# NB2_PSU.net
KiCad netlist of a schematic drawn in Altium Designer
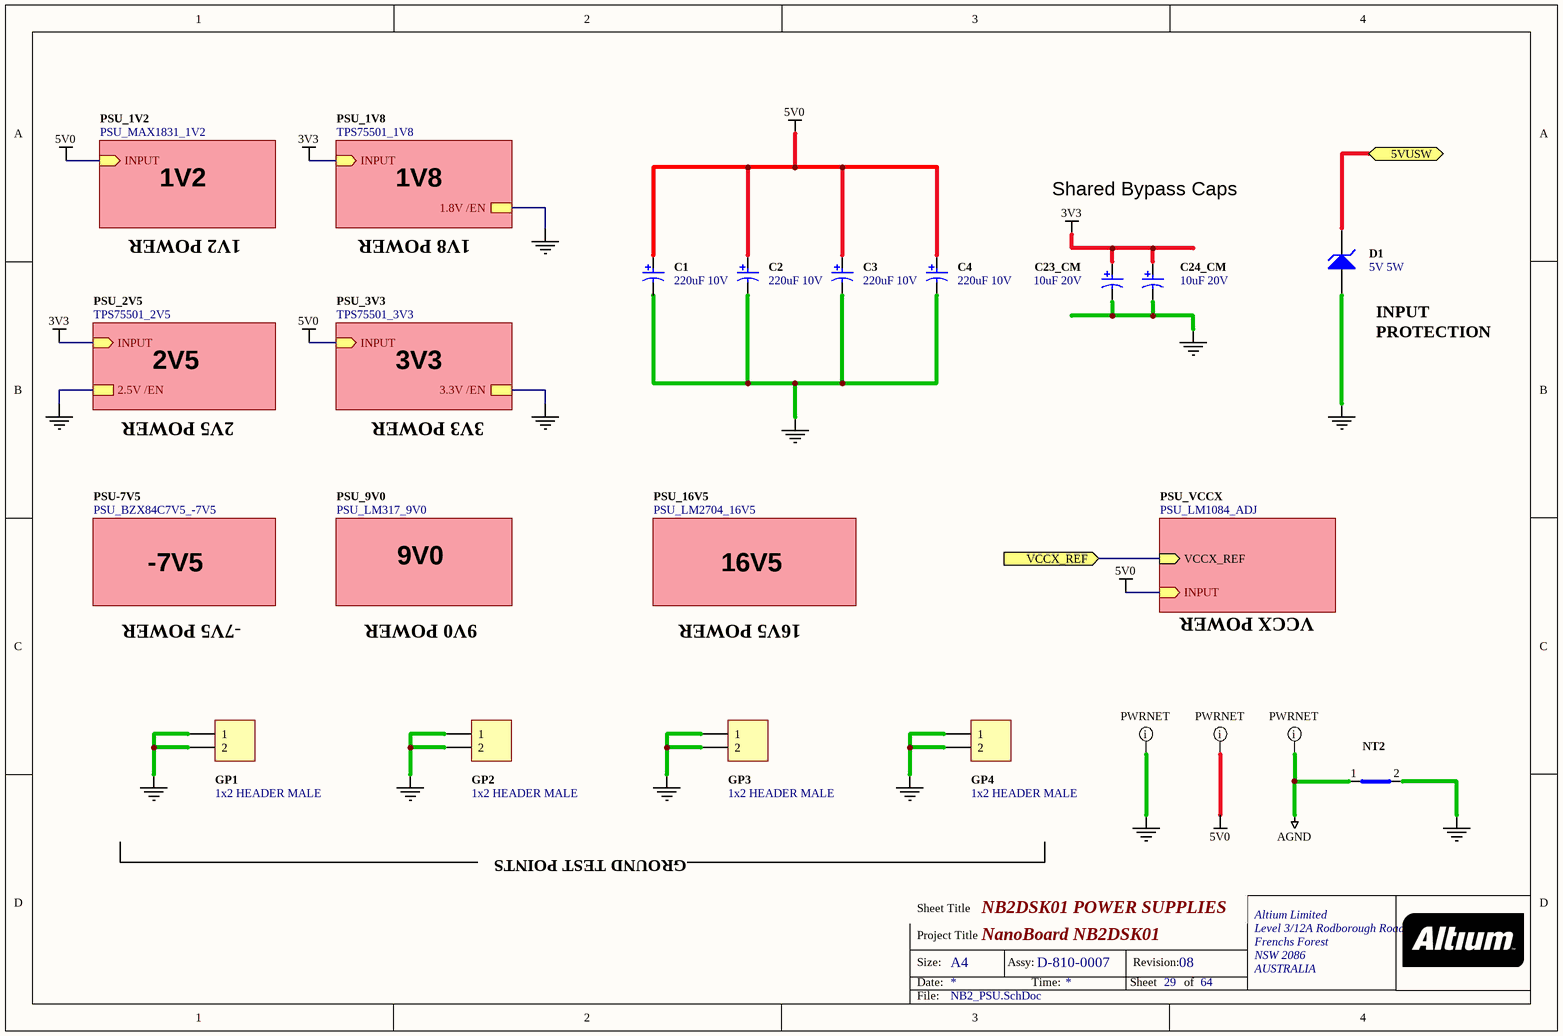
[diagram p0: NB2_PSU.SchDoc]

(export (version "E")
  (design (tool "Eeschema 10.0.6"))
  (components
    (comp (ref "C1")
      (value "220uF 10V")
      (footprint "CAPC7343-STAR")
      (description "Capacitor, Tantalum, 220uF 10% 10V MCCT-D (7343-31)")
      (fields (field (name "TOLERANCE") "10 %"))
      (libsource (lib "altium-import") (part "root_0_CAP-P_"))
    )
    (comp (ref "C2")
      (value "220uF 10V")
      (footprint "CAPC7343-STAR")
      (description "Capacitor, Tantalum, 220uF 10% 10V MCCT-D (7343-31)")
      (fields (field (name "TOLERANCE") "10 %"))
      (libsource (lib "altium-import") (part "root_0_CAP-P_"))
    )
    (comp (ref "C3")
      (value "220uF 10V")
      (footprint "CAPC7343-STAR")
      (description "Capacitor, Tantalum, 220uF 10% 10V MCCT-D (7343-31)")
      (fields (field (name "TOLERANCE") "10 %"))
      (libsource (lib "altium-import") (part "root_0_CAP-P_"))
    )
    (comp (ref "C4")
      (value "220uF 10V")
      (footprint "CAPC7343-STAR")
      (description "Capacitor, Tantalum, 220uF 10% 10V MCCT-D (7343-31)")
      (fields (field (name "TOLERANCE") "10 %"))
      (libsource (lib "altium-import") (part "root_0_CAP-P_"))
    )
    (comp (ref "C23_CM")
      (value "10uF 20V")
      (footprint "CAPC3528-STAR")
      (description "Capacitor, Tantalum, 10uF 10% 20V MCCT-B (3528)")
      (fields (field (name "TOLERANCE") "10 %"))
      (libsource (lib "altium-import") (part "root_0_CAP-P_"))
    )
    (comp (ref "C24_CM")
      (value "10uF 20V")
      (footprint "CAPC3528-STAR")
      (description "Capacitor, Tantalum, 10uF 10% 20V MCCT-B (3528)")
      (fields (field (name "TOLERANCE") "10 %"))
      (libsource (lib "altium-import") (part "root_0_CAP-P_"))
    )
    (comp (ref "D1")
      (value "5V 5W")
      (footprint "DIOM8059")
      (description "Zener Diode, 5V 5W")
      (libsource (lib "altium-import") (part "root_1_DIO-ZENER-1-2_"))
    )
    (comp (ref "GP1")
      (value "1x2 HEADER MALE")
      (footprint "HDR1X2")
      (description "Header IDC, 2 x 1 Pin Vertical 2.54mm Pitch (Non-Boxed, Male)")
      (libsource (lib "altium-import") (part "root_0_CON-HDR-1x2-STR_"))
    )
    (comp (ref "GP2")
      (value "1x2 HEADER MALE")
      (footprint "HDR1X2")
      (description "Header IDC, 2 x 1 Pin Vertical 2.54mm Pitch (Non-Boxed, Male)")
      (libsource (lib "altium-import") (part "root_0_CON-HDR-1x2-STR_"))
    )
    (comp (ref "GP3")
      (value "1x2 HEADER MALE")
      (footprint "HDR1X2")
      (description "Header IDC, 2 x 1 Pin Vertical 2.54mm Pitch (Non-Boxed, Male)")
      (libsource (lib "altium-import") (part "root_0_CON-HDR-1x2-STR_"))
    )
    (comp (ref "GP4")
      (value "1x2 HEADER MALE")
      (footprint "HDR1X2")
      (description "Header IDC, 2 x 1 Pin Vertical 2.54mm Pitch (Non-Boxed, Male)")
      (libsource (lib "altium-import") (part "root_0_CON-HDR-1x2-STR_"))
    )
    (comp (ref "NT2")
      (value "Net Tie SMT2")
      (footprint "NETTIE-SMT2-31X51")
      (description "Net-Tie, Surface Mount, 2 x 1.6mm x 0.8mm SMT Pads - For 0.8mm Track")
      (libsource (lib "AltiumDesignLibrary") (part "NETTIE-SMT2"))
    )
  )
  (nets
    (net (code "1") (name "/5VUSW") (class "Default")
      (node (ref "D1") (pin "2") (pinfunction "K_2") (pintype "passive"))
    )
    (net (code "3") (name "3V3") (class "Default")
      (node (ref "C23_CM") (pin "1") (pinfunction "1_1") (pintype "passive"))
      (node (ref "C24_CM") (pin "1") (pinfunction "1_1") (pintype "passive"))
    )
    (net (code "4") (name "5V0") (class "Default")
      (node (ref "C1") (pin "1") (pinfunction "1_1") (pintype "passive"))
      (node (ref "C2") (pin "1") (pinfunction "1_1") (pintype "passive"))
      (node (ref "C3") (pin "1") (pinfunction "1_1") (pintype "passive"))
      (node (ref "C4") (pin "1") (pinfunction "1_1") (pintype "passive"))
    )
    (net (code "5") (name "AGND") (class "Default")
      (node (ref "NT2") (pin "1") (pinfunction "Net1_1") (pintype "passive"))
    )
    (net (code "6") (name "GND") (class "Default")
      (node (ref "C1") (pin "2") (pinfunction "2_2") (pintype "passive"))
      (node (ref "C2") (pin "2") (pinfunction "2_2") (pintype "passive"))
      (node (ref "C23_CM") (pin "2") (pinfunction "2_2") (pintype "passive"))
      (node (ref "C24_CM") (pin "2") (pinfunction "2_2") (pintype "passive"))
      (node (ref "C3") (pin "2") (pinfunction "2_2") (pintype "passive"))
      (node (ref "C4") (pin "2") (pinfunction "2_2") (pintype "passive"))
      (node (ref "D1") (pin "1") (pinfunction "A_1") (pintype "passive"))
      (node (ref "GP1") (pin "1") (pinfunction "1_1") (pintype "passive"))
      (node (ref "GP1") (pin "2") (pinfunction "2_2") (pintype "passive"))
      (node (ref "GP2") (pin "1") (pinfunction "1_1") (pintype "passive"))
      (node (ref "GP2") (pin "2") (pinfunction "2_2") (pintype "passive"))
      (node (ref "GP3") (pin "1") (pinfunction "1_1") (pintype "passive"))
      (node (ref "GP3") (pin "2") (pinfunction "2_2") (pintype "passive"))
      (node (ref "GP4") (pin "1") (pinfunction "1_1") (pintype "passive"))
      (node (ref "GP4") (pin "2") (pinfunction "2_2") (pintype "passive"))
      (node (ref "NT2") (pin "2") (pinfunction "Net2_2") (pintype "passive"))
    )
  )
)
